# Peripherals.net
KiCad netlist of a schematic drawn in Altium Designer
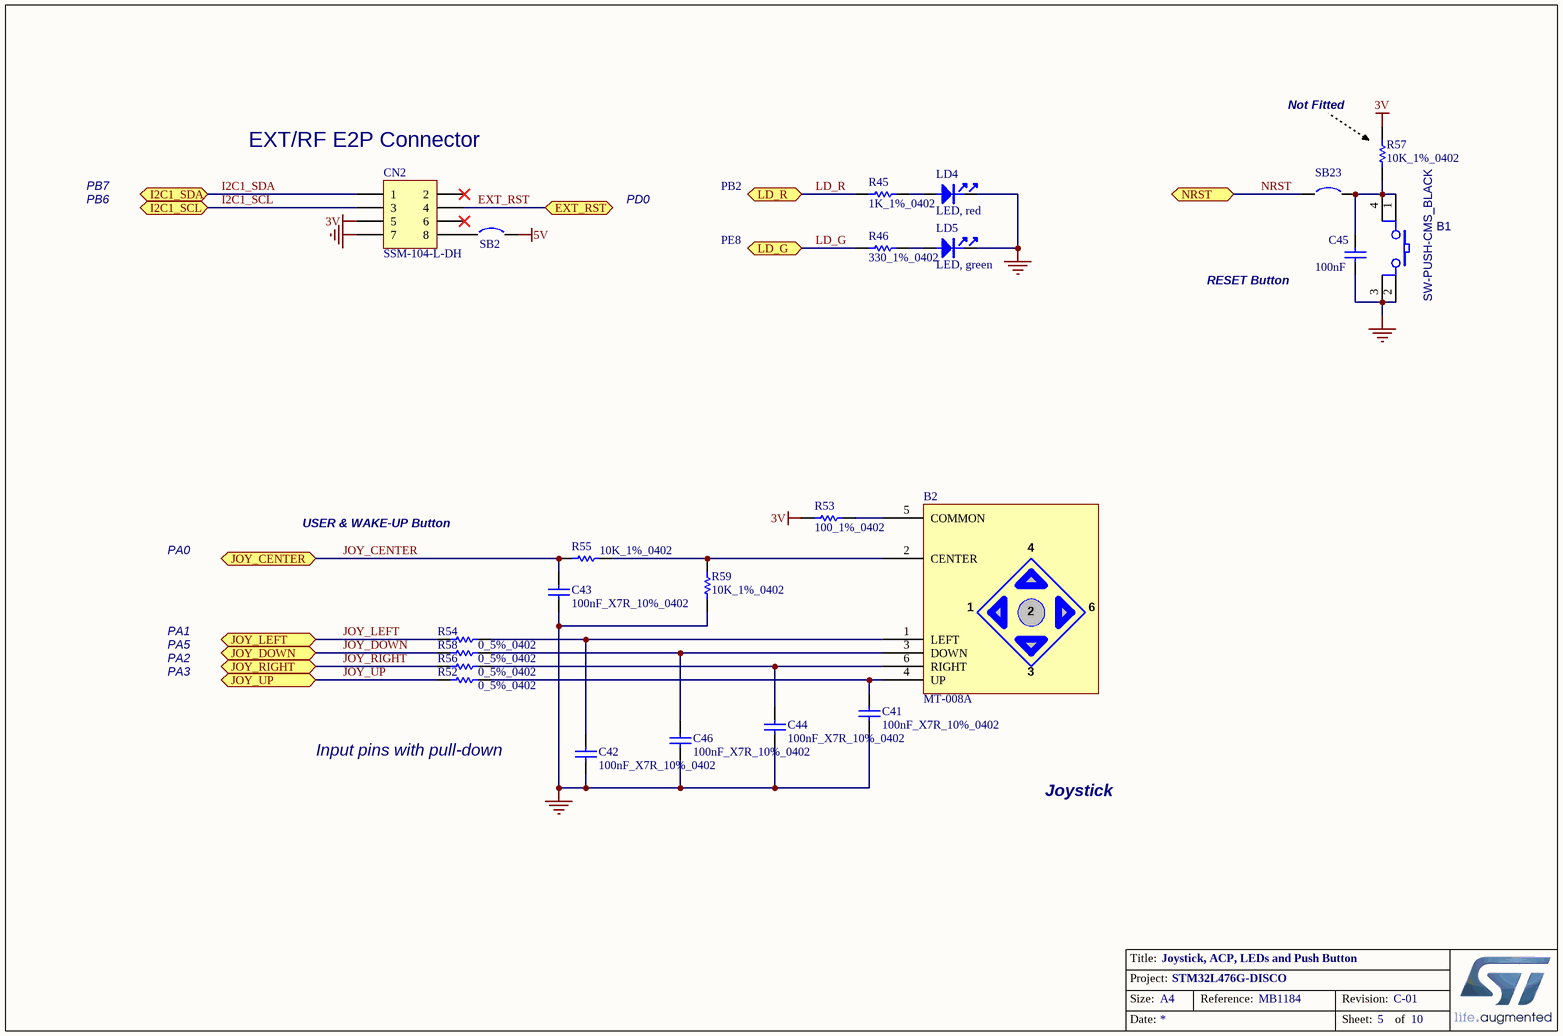
[diagram p0: Peripherals.SchDoc]

(export (version "E")
  (design (tool "Eeschema 10.0.6"))
  (components
    (comp (ref "B1")
      (value "SW-PUSH-CMS_BLACK")
      (footprint "BP1CMS")
      (description "Non-Open Push Button,Black 0.1A 24V,Square head,6*6,SMT,180Degree,TD-0341X-GO1,wealthmetal")
      (libsource (lib "MCD_TOOLS") (part "SW-PUSH-CMS_BLACK"))
    )
    (comp (ref "B2")
      (value "MT-008A")
      (footprint "MT-008A")
      (description "Joystick with Hat, Multi Function Switch")
      (libsource (lib "MCD_TOOLS") (part "MT-008A"))
    )
    (comp (ref "C41")
      (value "100nF_X7R_10%_0402")
      (footprint "0402C")
      (description "Capacitor,100nF,16V,X7R,10%,0402,YAGEO")
      (libsource (lib "MCD_TOOLS") (part "Cap_100nF_X7R_10%_0402"))
    )
    (comp (ref "C42")
      (value "100nF_X7R_10%_0402")
      (footprint "0402C")
      (description "Capacitor,100nF,16V,X7R,10%,0402,YAGEO")
      (libsource (lib "MCD_TOOLS") (part "Cap_100nF_X7R_10%_0402"))
    )
    (comp (ref "C43")
      (value "100nF_X7R_10%_0402")
      (footprint "0402C")
      (description "Capacitor,100nF,16V,X7R,10%,0402,YAGEO")
      (libsource (lib "MCD_TOOLS") (part "Cap_100nF_X7R_10%_0402"))
    )
    (comp (ref "C44")
      (value "100nF_X7R_10%_0402")
      (footprint "0402C")
      (description "Capacitor,100nF,16V,X7R,10%,0402,YAGEO")
      (libsource (lib "MCD_TOOLS") (part "Cap_100nF_X7R_10%_0402"))
    )
    (comp (ref "C45")
      (value "100nF")
      (footprint "0402C")
      (description "Capacitor,100nF,16V,X7R,10%,0402,YAGEO")
      (libsource (lib "MCD_TOOLS") (part "Cap_100nF_X7R_10%_0402"))
    )
    (comp (ref "C46")
      (value "100nF_X7R_10%_0402")
      (footprint "0402C")
      (description "Capacitor,100nF,16V,X7R,10%,0402,YAGEO")
      (libsource (lib "MCD_TOOLS") (part "Cap_100nF_X7R_10%_0402"))
    )
    (comp (ref "CN2")
      (value "SSM-104-L-DH")
      (footprint "SSM-104-L-DH")
      (description "Header, 5-Pin, Dual row")
      (fields (field (name "PUBLISHER") "Altium Limited"))
      (libsource (lib "mb1045") (part "SSM-104-L-DH"))
    )
    (comp (ref "LD4")
      (value "LED, red")
      (footprint "0603D")
      (description "LED,red,0603,19-213-R6C-AP1Q2B/3T,everlight")
      (libsource (lib "MCD_TOOLS") (part "LED_red"))
    )
    (comp (ref "LD5")
      (value "LED, green")
      (footprint "0603D")
      (description "LED,green,0603,19-213SYGC/S530-E2/TR8,everlight")
      (libsource (lib "MCD_TOOLS") (part "LED_green"))
    )
    (comp (ref "R45")
      (value "1K_1%_0402")
      (footprint "0402R")
      (description "Resistor,1K,0402,1%,YAGEO")
      (libsource (lib "MCD_TOOLS") (part "Res_1K_1%_0402"))
    )
    (comp (ref "R46")
      (value "330_1%_0402")
      (footprint "0402R")
      (description "Resistor,330,0402,1%,YAGEO")
      (libsource (lib "MCD_TOOLS") (part "Res_330_1%_0402"))
    )
    (comp (ref "R52")
      (value "0_5%_0402")
      (footprint "0402R")
      (description "Resistor,0,0402,5%,YAGEO")
      (libsource (lib "MCD_TOOLS") (part "Res_0_5%_0402"))
    )
    (comp (ref "R53")
      (value "100_1%_0402")
      (footprint "0402R")
      (description "Resistor,100,0402,1%,YAGEO")
      (libsource (lib "MCD_TOOLS") (part "Res_100_1%_0402"))
    )
    (comp (ref "R54")
      (value "0_5%_0402")
      (footprint "0402R")
      (description "Resistor,0,0402,5%,YAGEO")
      (libsource (lib "MCD_TOOLS") (part "Res_0_5%_0402"))
    )
    (comp (ref "R55")
      (value "10K_1%_0402")
      (footprint "0402R")
      (description "Resistor,10K,0402,1%,YAGEO")
      (libsource (lib "MCD_TOOLS") (part "Res_10K_1%_0402"))
    )
    (comp (ref "R56")
      (value "0_5%_0402")
      (footprint "0402R")
      (description "Resistor,0,0402,5%,YAGEO")
      (libsource (lib "MCD_TOOLS") (part "Res_0_5%_0402"))
    )
    (comp (ref "R57")
      (value "10K_1%_0402")
      (footprint "0402R")
      (description "Resistor,10K,0402,1%,YAGEO")
      (libsource (lib "MCD_TOOLS") (part "Res_10K_1%_0402"))
    )
    (comp (ref "R58")
      (value "0_5%_0402")
      (footprint "0402R")
      (description "Resistor,0,0402,5%,YAGEO")
      (libsource (lib "MCD_TOOLS") (part "Res_0_5%_0402"))
    )
    (comp (ref "R59")
      (value "10K_1%_0402")
      (footprint "0402R")
      (description "Resistor,10K,0402,1%,YAGEO")
      (libsource (lib "MCD_TOOLS") (part "Res_10K_1%_0402"))
    )
    (comp (ref "SB2")
      (value "Circuit Breaker")
      (footprint "JP2_SMD")
      (libsource (lib "MCD_TOOLS") (part "Circuit Breaker"))
    )
    (comp (ref "SB23")
      (value "Circuit Breaker")
      (footprint "JP2_SMD")
      (libsource (lib "MCD_TOOLS") (part "Circuit Breaker"))
    )
  )
  (nets
    (net (code "1") (name "/EXT_RST") (class "Default")
      (node (ref "CN2") (pin "4") (pinfunction "4_4") (pintype "passive"))
    )
    (net (code "2") (name "/I2C1_SCL") (class "Default")
      (node (ref "CN2") (pin "3") (pinfunction "3_3") (pintype "passive"))
    )
    (net (code "3") (name "/I2C1_SDA") (class "Default")
      (node (ref "CN2") (pin "1") (pinfunction "1_1") (pintype "passive"))
    )
    (net (code "4") (name "/JOY_CENTER") (class "Default")
      (node (ref "C43") (pin "2") (pinfunction "2_2") (pintype "passive"))
      (node (ref "R55") (pin "1") (pinfunction "1_1") (pintype "passive"))
    )
    (net (code "5") (name "/JOY_DOWN") (class "Default")
      (node (ref "R58") (pin "1") (pinfunction "1_1") (pintype "passive"))
    )
    (net (code "6") (name "/JOY_LEFT") (class "Default")
      (node (ref "R54") (pin "1") (pinfunction "1_1") (pintype "passive"))
    )
    (net (code "7") (name "/JOY_RIGHT") (class "Default")
      (node (ref "R56") (pin "1") (pinfunction "1_1") (pintype "passive"))
    )
    (net (code "8") (name "/JOY_UP") (class "Default")
      (node (ref "R52") (pin "1") (pinfunction "1_1") (pintype "passive"))
    )
    (net (code "9") (name "/LD_G") (class "Default")
      (node (ref "R46") (pin "1") (pinfunction "1_1") (pintype "passive"))
    )
    (net (code "10") (name "/LD_R") (class "Default")
      (node (ref "R45") (pin "1") (pinfunction "1_1") (pintype "passive"))
    )
    (net (code "11") (name "/NRST") (class "Default")
      (node (ref "SB23") (pin "1") (pinfunction "1_1") (pintype "passive"))
    )
    (net (code "12") (name "3V") (class "Default")
      (node (ref "CN2") (pin "5") (pinfunction "5_5") (pintype "passive"))
      (node (ref "R53") (pin "1") (pinfunction "1_1") (pintype "passive"))
      (node (ref "R57") (pin "2") (pinfunction "2_2") (pintype "passive"))
    )
    (net (code "13") (name "5V") (class "Default")
      (node (ref "SB2") (pin "2") (pinfunction "2_2") (pintype "passive"))
    )
    (net (code "14") (name "GND") (class "Default")
      (node (ref "B1") (pin "2") (pinfunction "2_2") (pintype "passive"))
      (node (ref "B1") (pin "3") (pinfunction "3_3") (pintype "passive"))
      (node (ref "C41") (pin "1") (pinfunction "1_1") (pintype "passive"))
      (node (ref "C42") (pin "1") (pinfunction "1_1") (pintype "passive"))
      (node (ref "C43") (pin "1") (pinfunction "1_1") (pintype "passive"))
      (node (ref "C44") (pin "1") (pinfunction "1_1") (pintype "passive"))
      (node (ref "C45") (pin "1") (pinfunction "1_1") (pintype "passive"))
      (node (ref "C46") (pin "1") (pinfunction "1_1") (pintype "passive"))
      (node (ref "CN2") (pin "7") (pinfunction "7_7") (pintype "passive"))
      (node (ref "LD4") (pin "2") (pintype "passive"))
      (node (ref "LD5") (pin "2") (pintype "passive"))
      (node (ref "R59") (pin "1") (pinfunction "1_1") (pintype "passive"))
    )
    (net (code "15") (name "Net-(B1-Pad1)") (class "Default")
      (node (ref "B1") (pin "1") (pinfunction "1_1") (pintype "passive"))
      (node (ref "B1") (pin "4") (pinfunction "4_4") (pintype "passive"))
      (node (ref "C45") (pin "2") (pinfunction "2_2") (pintype "passive"))
      (node (ref "R57") (pin "1") (pinfunction "1_1") (pintype "passive"))
      (node (ref "SB23") (pin "2") (pinfunction "2_2") (pintype "passive"))
    )
    (net (code "16") (name "Net-(B2-CENTER)") (class "Default")
      (node (ref "B2") (pin "2") (pinfunction "CENTER_2") (pintype "passive"))
      (node (ref "R55") (pin "2") (pinfunction "2_2") (pintype "passive"))
      (node (ref "R59") (pin "2") (pinfunction "2_2") (pintype "passive"))
    )
    (net (code "17") (name "Net-(B2-COMMON)") (class "Default")
      (node (ref "B2") (pin "5") (pinfunction "COMMON_5") (pintype "passive"))
      (node (ref "R53") (pin "2") (pinfunction "2_2") (pintype "passive"))
    )
    (net (code "18") (name "Net-(B2-DOWN)") (class "Default")
      (node (ref "B2") (pin "3") (pinfunction "DOWN_3") (pintype "passive"))
      (node (ref "C46") (pin "2") (pinfunction "2_2") (pintype "passive"))
      (node (ref "R58") (pin "2") (pinfunction "2_2") (pintype "passive"))
    )
    (net (code "19") (name "Net-(B2-LEFT)") (class "Default")
      (node (ref "B2") (pin "1") (pinfunction "LEFT_1") (pintype "passive"))
      (node (ref "C42") (pin "2") (pinfunction "2_2") (pintype "passive"))
      (node (ref "R54") (pin "2") (pinfunction "2_2") (pintype "passive"))
    )
    (net (code "20") (name "Net-(B2-RIGHT)") (class "Default")
      (node (ref "B2") (pin "6") (pinfunction "RIGHT_6") (pintype "passive"))
      (node (ref "C44") (pin "2") (pinfunction "2_2") (pintype "passive"))
      (node (ref "R56") (pin "2") (pinfunction "2_2") (pintype "passive"))
    )
    (net (code "21") (name "Net-(B2-UP)") (class "Default")
      (node (ref "B2") (pin "4") (pinfunction "UP_4") (pintype "passive"))
      (node (ref "C41") (pin "2") (pinfunction "2_2") (pintype "passive"))
      (node (ref "R52") (pin "2") (pinfunction "2_2") (pintype "passive"))
    )
    (net (code "22") (name "Net-(CN2-Pad8)") (class "Default")
      (node (ref "CN2") (pin "8") (pinfunction "8_8") (pintype "passive"))
      (node (ref "SB2") (pin "1") (pinfunction "1_1") (pintype "passive"))
    )
    (net (code "23") (name "Net-(LD4-Pad1)") (class "Default")
      (node (ref "LD4") (pin "1") (pintype "passive"))
      (node (ref "R45") (pin "2") (pinfunction "2_2") (pintype "passive"))
    )
    (net (code "24") (name "Net-(LD5-Pad1)") (class "Default")
      (node (ref "LD5") (pin "1") (pintype "passive"))
      (node (ref "R46") (pin "2") (pinfunction "2_2") (pintype "passive"))
    )
    (net (code "25") (name "unconnected-(CN2-Pad2)") (class "Default")
      (node (ref "CN2") (pin "2") (pinfunction "2_2") (pintype "passive+no_connect"))
    )
    (net (code "26") (name "unconnected-(CN2-Pad6)") (class "Default")
      (node (ref "CN2") (pin "6") (pinfunction "6_6") (pintype "passive+no_connect"))
    )
  )
)
